# Shematich_v1.net
KiCad netlist of a schematic drawn in EAGLE
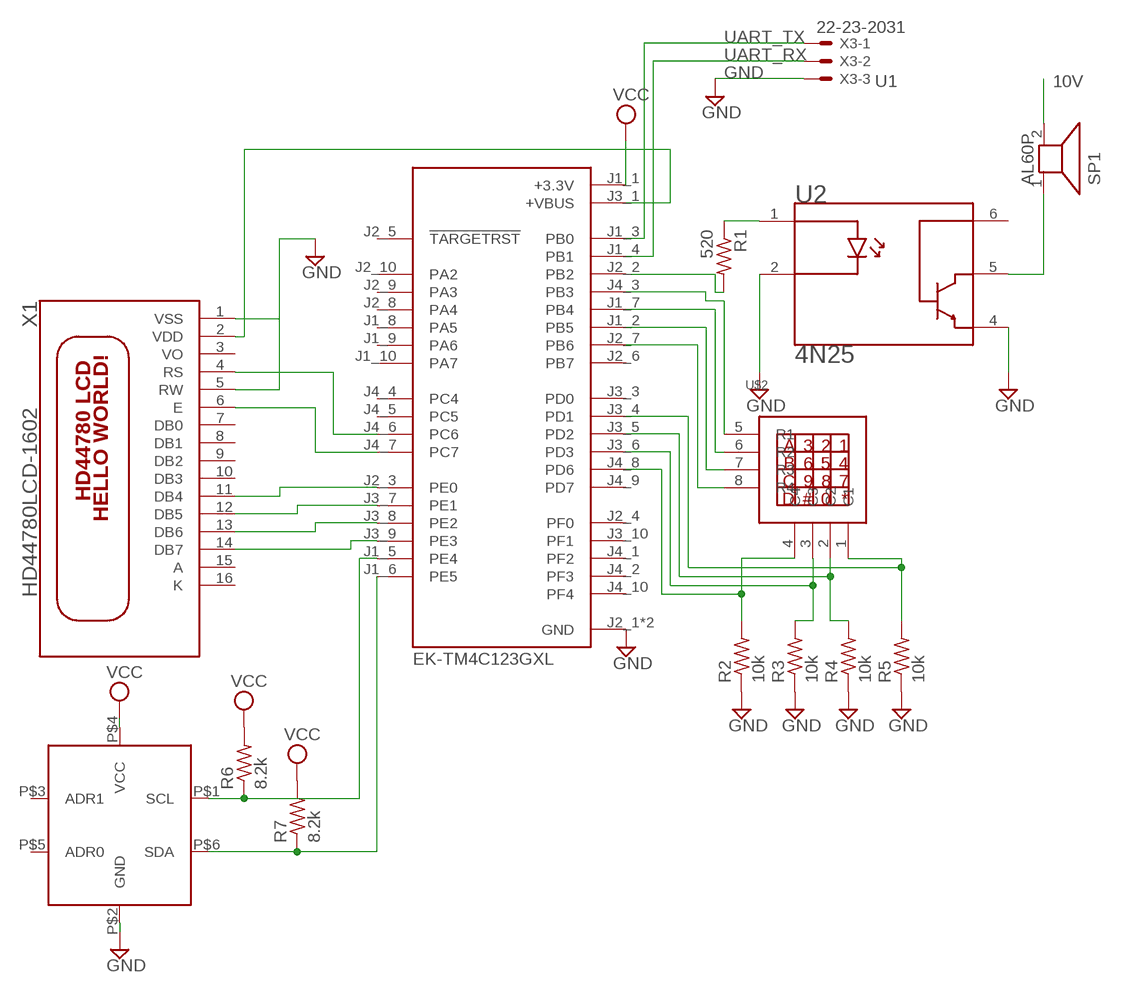
[diagram p0: schematic, sheet 1]

(export (version "E")
  (design (tool "Eeschema 10.0.6"))
  (components
    (comp (ref "R1")
      (value "520")
      (footprint "eagle-import:0204_7")
      (libsource (lib "eagle-import") (part "R-US_0204/7"))
    )
    (comp (ref "R2")
      (value "10k")
      (footprint "eagle-import:0204_7")
      (libsource (lib "eagle-import") (part "R-US_0204/7"))
    )
    (comp (ref "R3")
      (value "10k")
      (footprint "eagle-import:0204_7")
      (libsource (lib "eagle-import") (part "R-US_0204/7"))
    )
    (comp (ref "R4")
      (value "10k")
      (footprint "eagle-import:0204_7")
      (libsource (lib "eagle-import") (part "R-US_0204/7"))
    )
    (comp (ref "R5")
      (value "10k")
      (footprint "eagle-import:0204_7")
      (libsource (lib "eagle-import") (part "R-US_0204/7"))
    )
    (comp (ref "R6")
      (value "8.2k")
      (footprint "eagle-import:0204_7")
      (libsource (lib "eagle-import") (part "R-US_0204/7"))
    )
    (comp (ref "R7")
      (value "8.2k")
      (footprint "eagle-import:0204_7")
      (libsource (lib "eagle-import") (part "R-US_0204/7"))
    )
    (comp (ref "SP1")
      (value "AL60P")
      (footprint "eagle-import:AL60P")
      (libsource (lib "eagle-import") (part "AL60P"))
    )
    (comp (ref "U$1")
      (value "TMP100")
      (footprint "eagle-import:SOT23-6")
      (libsource (lib "eagle-import") (part "TMP100"))
    )
    (comp (ref "U$2")
      (value "KEYPAD4X4")
      (footprint "eagle-import:KEYPAD4X4")
      (libsource (lib "eagle-import") (part "KEYPAD4X4"))
    )
    (comp (ref "U1")
      (value "EK-TM4C123GXL")
      (footprint "eagle-import:MODULE_EK-TM4C123GXL")
      (fields (field (name "MF") "Texas Instruments"))
      (libsource (lib "eagle-import") (part "EK-TM4C123GXL"))
    )
    (comp (ref "U2")
      (value "4N25")
      (footprint "eagle-import:DIP762W50P254L712H400Q6N")
      (fields (field (name "MF") "Vishay Semiconductor"))
      (libsource (lib "eagle-import") (part "4N25"))
    )
    (comp (ref "X1")
      (value "HD44780LCD-1602")
      (footprint "eagle-import:LCD1602")
      (libsource (lib "eagle-import") (part "HD44780LCD-1602"))
    )
    (comp (ref "X3")
      (value "22-23-2031")
      (footprint "eagle-import:22-23-2031")
      (fields (field (name "MF") "MOLEX"))
      (libsource (lib "eagle-import") (part "22-23-2031"))
    )
  )
  (nets
    (net (code "1") (name "/10V") (class "Default")
      (node (ref "SP1") (pin "2") (pinfunction "2_2") (pintype "passive"))
    )
    (net (code "2") (name "/UART_RX") (class "Default")
      (node (ref "U1") (pin "J1_4") (pinfunction "PB1_J1_4") (pintype "bidirectional"))
      (node (ref "X3") (pin "2") (pinfunction "S_2") (pintype "passive"))
    )
    (net (code "3") (name "/UART_TX") (class "Default")
      (node (ref "U1") (pin "J1_3") (pinfunction "PB0_J1_3") (pintype "bidirectional"))
      (node (ref "X3") (pin "1") (pinfunction "S_1") (pintype "passive"))
    )
    (net (code "4") (name "GND") (class "Default")
      (node (ref "R2") (pin "1") (pinfunction "1_1") (pintype "passive"))
      (node (ref "R3") (pin "1") (pinfunction "1_1") (pintype "passive"))
      (node (ref "R4") (pin "1") (pinfunction "1_1") (pintype "passive"))
      (node (ref "R5") (pin "1") (pinfunction "1_1") (pintype "passive"))
      (node (ref "U$1") (pin "P$2") (pinfunction "GND_P$2") (pintype "power_in"))
      (node (ref "U1") (pin "J2_1") (pinfunction "GND_J2_1") (pintype "power_in"))
      (node (ref "U1") (pin "J3_2") (pinfunction "GND_J3_2") (pintype "power_in"))
      (node (ref "U2") (pin "2") (pinfunction "K_2") (pintype "passive"))
      (node (ref "U2") (pin "4") (pinfunction "E_4") (pintype "passive"))
      (node (ref "X1") (pin "1") (pinfunction "VSS_1") (pintype "power_in"))
      (node (ref "X1") (pin "5") (pinfunction "RW_5") (pintype "input"))
      (node (ref "X3") (pin "3") (pinfunction "S_3") (pintype "passive"))
    )
    (net (code "5") (name "Net-(U$1-SCL)") (class "Default")
      (node (ref "R6") (pin "1") (pinfunction "1_1") (pintype "passive"))
      (node (ref "U$1") (pin "P$1") (pinfunction "SCL_P$1") (pintype "bidirectional"))
      (node (ref "U1") (pin "J1_5") (pinfunction "PE4_J1_5") (pintype "bidirectional"))
    )
    (net (code "6") (name "Net-(U$1-SDA)") (class "Default")
      (node (ref "R7") (pin "1") (pinfunction "1_1") (pintype "passive"))
      (node (ref "U$1") (pin "P$6") (pinfunction "SDA_P$6") (pintype "bidirectional"))
      (node (ref "U1") (pin "J1_6") (pinfunction "PE5_J1_6") (pintype "bidirectional"))
    )
    (net (code "7") (name "Net-(U$2-C1)") (class "Default")
      (node (ref "R5") (pin "2") (pinfunction "2_2") (pintype "passive"))
      (node (ref "U$2") (pin "1") (pinfunction "C1_1") (pintype "bidirectional"))
      (node (ref "U1") (pin "J3_4") (pinfunction "PD1_J3_4") (pintype "bidirectional"))
    )
    (net (code "8") (name "Net-(U$2-C2)") (class "Default")
      (node (ref "R4") (pin "2") (pinfunction "2_2") (pintype "passive"))
      (node (ref "U$2") (pin "2") (pinfunction "C2_2") (pintype "bidirectional"))
      (node (ref "U1") (pin "J3_5") (pinfunction "PD2_J3_5") (pintype "bidirectional"))
    )
    (net (code "9") (name "Net-(U$2-C3)") (class "Default")
      (node (ref "R3") (pin "2") (pinfunction "2_2") (pintype "passive"))
      (node (ref "U$2") (pin "3") (pinfunction "C3_3") (pintype "bidirectional"))
      (node (ref "U1") (pin "J3_6") (pinfunction "PD3_J3_6") (pintype "bidirectional"))
    )
    (net (code "10") (name "Net-(U$2-C4)") (class "Default")
      (node (ref "R2") (pin "2") (pinfunction "2_2") (pintype "passive"))
      (node (ref "U$2") (pin "4") (pinfunction "C4_4") (pintype "bidirectional"))
      (node (ref "U1") (pin "J4_8") (pinfunction "PD6_J4_8") (pintype "bidirectional"))
    )
    (net (code "11") (name "Net-(U$2-R1)") (class "Default")
      (node (ref "U$2") (pin "5") (pinfunction "R1_5") (pintype "bidirectional"))
      (node (ref "U1") (pin "J4_3") (pinfunction "PB3_J4_3") (pintype "bidirectional"))
    )
    (net (code "12") (name "Net-(U$2-R2)") (class "Default")
      (node (ref "U$2") (pin "6") (pinfunction "R2_6") (pintype "bidirectional"))
      (node (ref "U1") (pin "J1_7") (pinfunction "PB4_J1_7") (pintype "bidirectional"))
    )
    (net (code "13") (name "Net-(U$2-R3)") (class "Default")
      (node (ref "U$2") (pin "7") (pinfunction "R3_7") (pintype "bidirectional"))
      (node (ref "U1") (pin "J1_2") (pinfunction "PB5_J1_2") (pintype "bidirectional"))
    )
    (net (code "14") (name "Net-(U$2-R4)") (class "Default")
      (node (ref "U$2") (pin "8") (pinfunction "R4_8") (pintype "bidirectional"))
      (node (ref "U1") (pin "J2_7") (pinfunction "PB6_J2_7") (pintype "bidirectional"))
    )
    (net (code "15") (name "Net-(U1-+VBUS)") (class "Default")
      (node (ref "U1") (pin "J3_1") (pinfunction "+VBUS_J3_1") (pintype "power_in"))
      (node (ref "X1") (pin "2") (pinfunction "VDD_2") (pintype "power_in"))
    )
    (net (code "16") (name "Net-(U1-PB2)") (class "Default")
      (node (ref "R1") (pin "2") (pinfunction "2_2") (pintype "passive"))
      (node (ref "U1") (pin "J2_2") (pinfunction "PB2_J2_2") (pintype "bidirectional"))
    )
    (net (code "17") (name "Net-(U1-PC6)") (class "Default")
      (node (ref "U1") (pin "J4_6") (pinfunction "PC6_J4_6") (pintype "bidirectional"))
      (node (ref "X1") (pin "4") (pinfunction "RS_4") (pintype "input"))
    )
    (net (code "18") (name "Net-(U1-PC7)") (class "Default")
      (node (ref "U1") (pin "J4_7") (pinfunction "PC7_J4_7") (pintype "bidirectional"))
      (node (ref "X1") (pin "6") (pinfunction "E_6") (pintype "input"))
    )
    (net (code "19") (name "Net-(U1-PE0)") (class "Default")
      (node (ref "U1") (pin "J2_3") (pinfunction "PE0_J2_3") (pintype "bidirectional"))
      (node (ref "X1") (pin "11") (pinfunction "DB4_11") (pintype "bidirectional"))
    )
    (net (code "20") (name "Net-(U1-PE1)") (class "Default")
      (node (ref "U1") (pin "J3_7") (pinfunction "PE1_J3_7") (pintype "bidirectional"))
      (node (ref "X1") (pin "12") (pinfunction "DB5_12") (pintype "bidirectional"))
    )
    (net (code "21") (name "Net-(U1-PE2)") (class "Default")
      (node (ref "U1") (pin "J3_8") (pinfunction "PE2_J3_8") (pintype "bidirectional"))
      (node (ref "X1") (pin "13") (pinfunction "DB6_13") (pintype "bidirectional"))
    )
    (net (code "22") (name "Net-(U1-PE3)") (class "Default")
      (node (ref "U1") (pin "J3_9") (pinfunction "PE3_J3_9") (pintype "bidirectional"))
      (node (ref "X1") (pin "14") (pinfunction "DB7_14") (pintype "bidirectional"))
    )
    (net (code "23") (name "Net-(U2-A)") (class "Default")
      (node (ref "R1") (pin "1") (pinfunction "1_1") (pintype "passive"))
      (node (ref "U2") (pin "1") (pinfunction "A_1") (pintype "passive"))
    )
    (net (code "24") (name "Net-(U2-C)") (class "Default")
      (node (ref "SP1") (pin "1") (pinfunction "1_1") (pintype "passive"))
      (node (ref "U2") (pin "5") (pinfunction "C_5") (pintype "passive"))
    )
    (net (code "25") (name "VCC") (class "Default")
      (node (ref "R6") (pin "2") (pinfunction "2_2") (pintype "passive"))
      (node (ref "R7") (pin "2") (pinfunction "2_2") (pintype "passive"))
      (node (ref "U$1") (pin "P$4") (pinfunction "VCC_P$4") (pintype "power_in"))
      (node (ref "U1") (pin "J1_1") (pinfunction "+3.3V_J1_1") (pintype "power_in"))
    )
    (net (code "26") (name "unconnected-(U$1-ADR0-PadP$5)") (class "Default")
      (node (ref "U$1") (pin "P$5") (pinfunction "ADR0_P$5") (pintype "bidirectional"))
    )
    (net (code "27") (name "unconnected-(U$1-ADR1-PadP$3)") (class "Default")
      (node (ref "U$1") (pin "P$3") (pinfunction "ADR1_P$3") (pintype "bidirectional"))
    )
    (net (code "28") (name "unconnected-(U1-PA2-PadJ2_10)") (class "Default")
      (node (ref "U1") (pin "J2_10") (pinfunction "PA2_J2_10") (pintype "bidirectional"))
    )
    (net (code "29") (name "unconnected-(U1-PA3-PadJ2_9)") (class "Default")
      (node (ref "U1") (pin "J2_9") (pinfunction "PA3_J2_9") (pintype "bidirectional"))
    )
    (net (code "30") (name "unconnected-(U1-PA4-PadJ2_8)") (class "Default")
      (node (ref "U1") (pin "J2_8") (pinfunction "PA4_J2_8") (pintype "bidirectional"))
    )
    (net (code "31") (name "unconnected-(U1-PA5-PadJ1_8)") (class "Default")
      (node (ref "U1") (pin "J1_8") (pinfunction "PA5_J1_8") (pintype "bidirectional"))
    )
    (net (code "32") (name "unconnected-(U1-PA6-PadJ1_9)") (class "Default")
      (node (ref "U1") (pin "J1_9") (pinfunction "PA6_J1_9") (pintype "bidirectional"))
    )
    (net (code "33") (name "unconnected-(U1-PA7-PadJ1_10)") (class "Default")
      (node (ref "U1") (pin "J1_10") (pinfunction "PA7_J1_10") (pintype "bidirectional"))
    )
    (net (code "34") (name "unconnected-(U1-PB7-PadJ2_6)") (class "Default")
      (node (ref "U1") (pin "J2_6") (pinfunction "PB7_J2_6") (pintype "bidirectional"))
    )
    (net (code "35") (name "unconnected-(U1-PC4-PadJ4_4)") (class "Default")
      (node (ref "U1") (pin "J4_4") (pinfunction "PC4_J4_4") (pintype "bidirectional"))
    )
    (net (code "36") (name "unconnected-(U1-PC5-PadJ4_5)") (class "Default")
      (node (ref "U1") (pin "J4_5") (pinfunction "PC5_J4_5") (pintype "bidirectional"))
    )
    (net (code "37") (name "unconnected-(U1-PD0-PadJ3_3)") (class "Default")
      (node (ref "U1") (pin "J3_3") (pinfunction "PD0_J3_3") (pintype "bidirectional"))
    )
    (net (code "38") (name "unconnected-(U1-PD7-PadJ4_9)") (class "Default")
      (node (ref "U1") (pin "J4_9") (pinfunction "PD7_J4_9") (pintype "bidirectional"))
    )
    (net (code "39") (name "unconnected-(U1-PF0-PadJ2_4)") (class "Default")
      (node (ref "U1") (pin "J2_4") (pinfunction "PF0_J2_4") (pintype "bidirectional"))
    )
    (net (code "40") (name "unconnected-(U1-PF1-PadJ3_10)") (class "Default")
      (node (ref "U1") (pin "J3_10") (pinfunction "PF1_J3_10") (pintype "bidirectional"))
    )
    (net (code "41") (name "unconnected-(U1-PF2-PadJ4_1)") (class "Default")
      (node (ref "U1") (pin "J4_1") (pinfunction "PF2_J4_1") (pintype "bidirectional"))
    )
    (net (code "42") (name "unconnected-(U1-PF3-PadJ4_2)") (class "Default")
      (node (ref "U1") (pin "J4_2") (pinfunction "PF3_J4_2") (pintype "bidirectional"))
    )
    (net (code "43") (name "unconnected-(U1-PF4-PadJ4_10)") (class "Default")
      (node (ref "U1") (pin "J4_10") (pinfunction "PF4_J4_10") (pintype "bidirectional"))
    )
    (net (code "44") (name "unconnected-(U1-~{TARGETRST}-PadJ2_5)") (class "Default")
      (node (ref "U1") (pin "J2_5") (pinfunction "~{TARGETRST}_J2_5") (pintype "input"))
    )
    (net (code "45") (name "unconnected-(U2-B-Pad6)") (class "Default")
      (node (ref "U2") (pin "6") (pinfunction "B_6") (pintype "passive"))
    )
    (net (code "46") (name "unconnected-(X1-A-Pad15)") (class "Default")
      (node (ref "X1") (pin "15") (pinfunction "A_15") (pintype "input"))
    )
    (net (code "47") (name "unconnected-(X1-DB0-Pad7)") (class "Default")
      (node (ref "X1") (pin "7") (pinfunction "DB0_7") (pintype "bidirectional"))
    )
    (net (code "48") (name "unconnected-(X1-DB1-Pad8)") (class "Default")
      (node (ref "X1") (pin "8") (pinfunction "DB1_8") (pintype "bidirectional"))
    )
    (net (code "49") (name "unconnected-(X1-DB2-Pad9)") (class "Default")
      (node (ref "X1") (pin "9") (pinfunction "DB2_9") (pintype "bidirectional"))
    )
    (net (code "50") (name "unconnected-(X1-DB3-Pad10)") (class "Default")
      (node (ref "X1") (pin "10") (pinfunction "DB3_10") (pintype "bidirectional"))
    )
    (net (code "51") (name "unconnected-(X1-K-Pad16)") (class "Default")
      (node (ref "X1") (pin "16") (pinfunction "K_16") (pintype "input"))
    )
    (net (code "52") (name "unconnected-(X1-VO-Pad3)") (class "Default")
      (node (ref "X1") (pin "3") (pinfunction "VO_3") (pintype "input"))
    )
  )
)
